# pa-test-board_V2.net
KiCad netlist of a schematic drawn in EAGLE
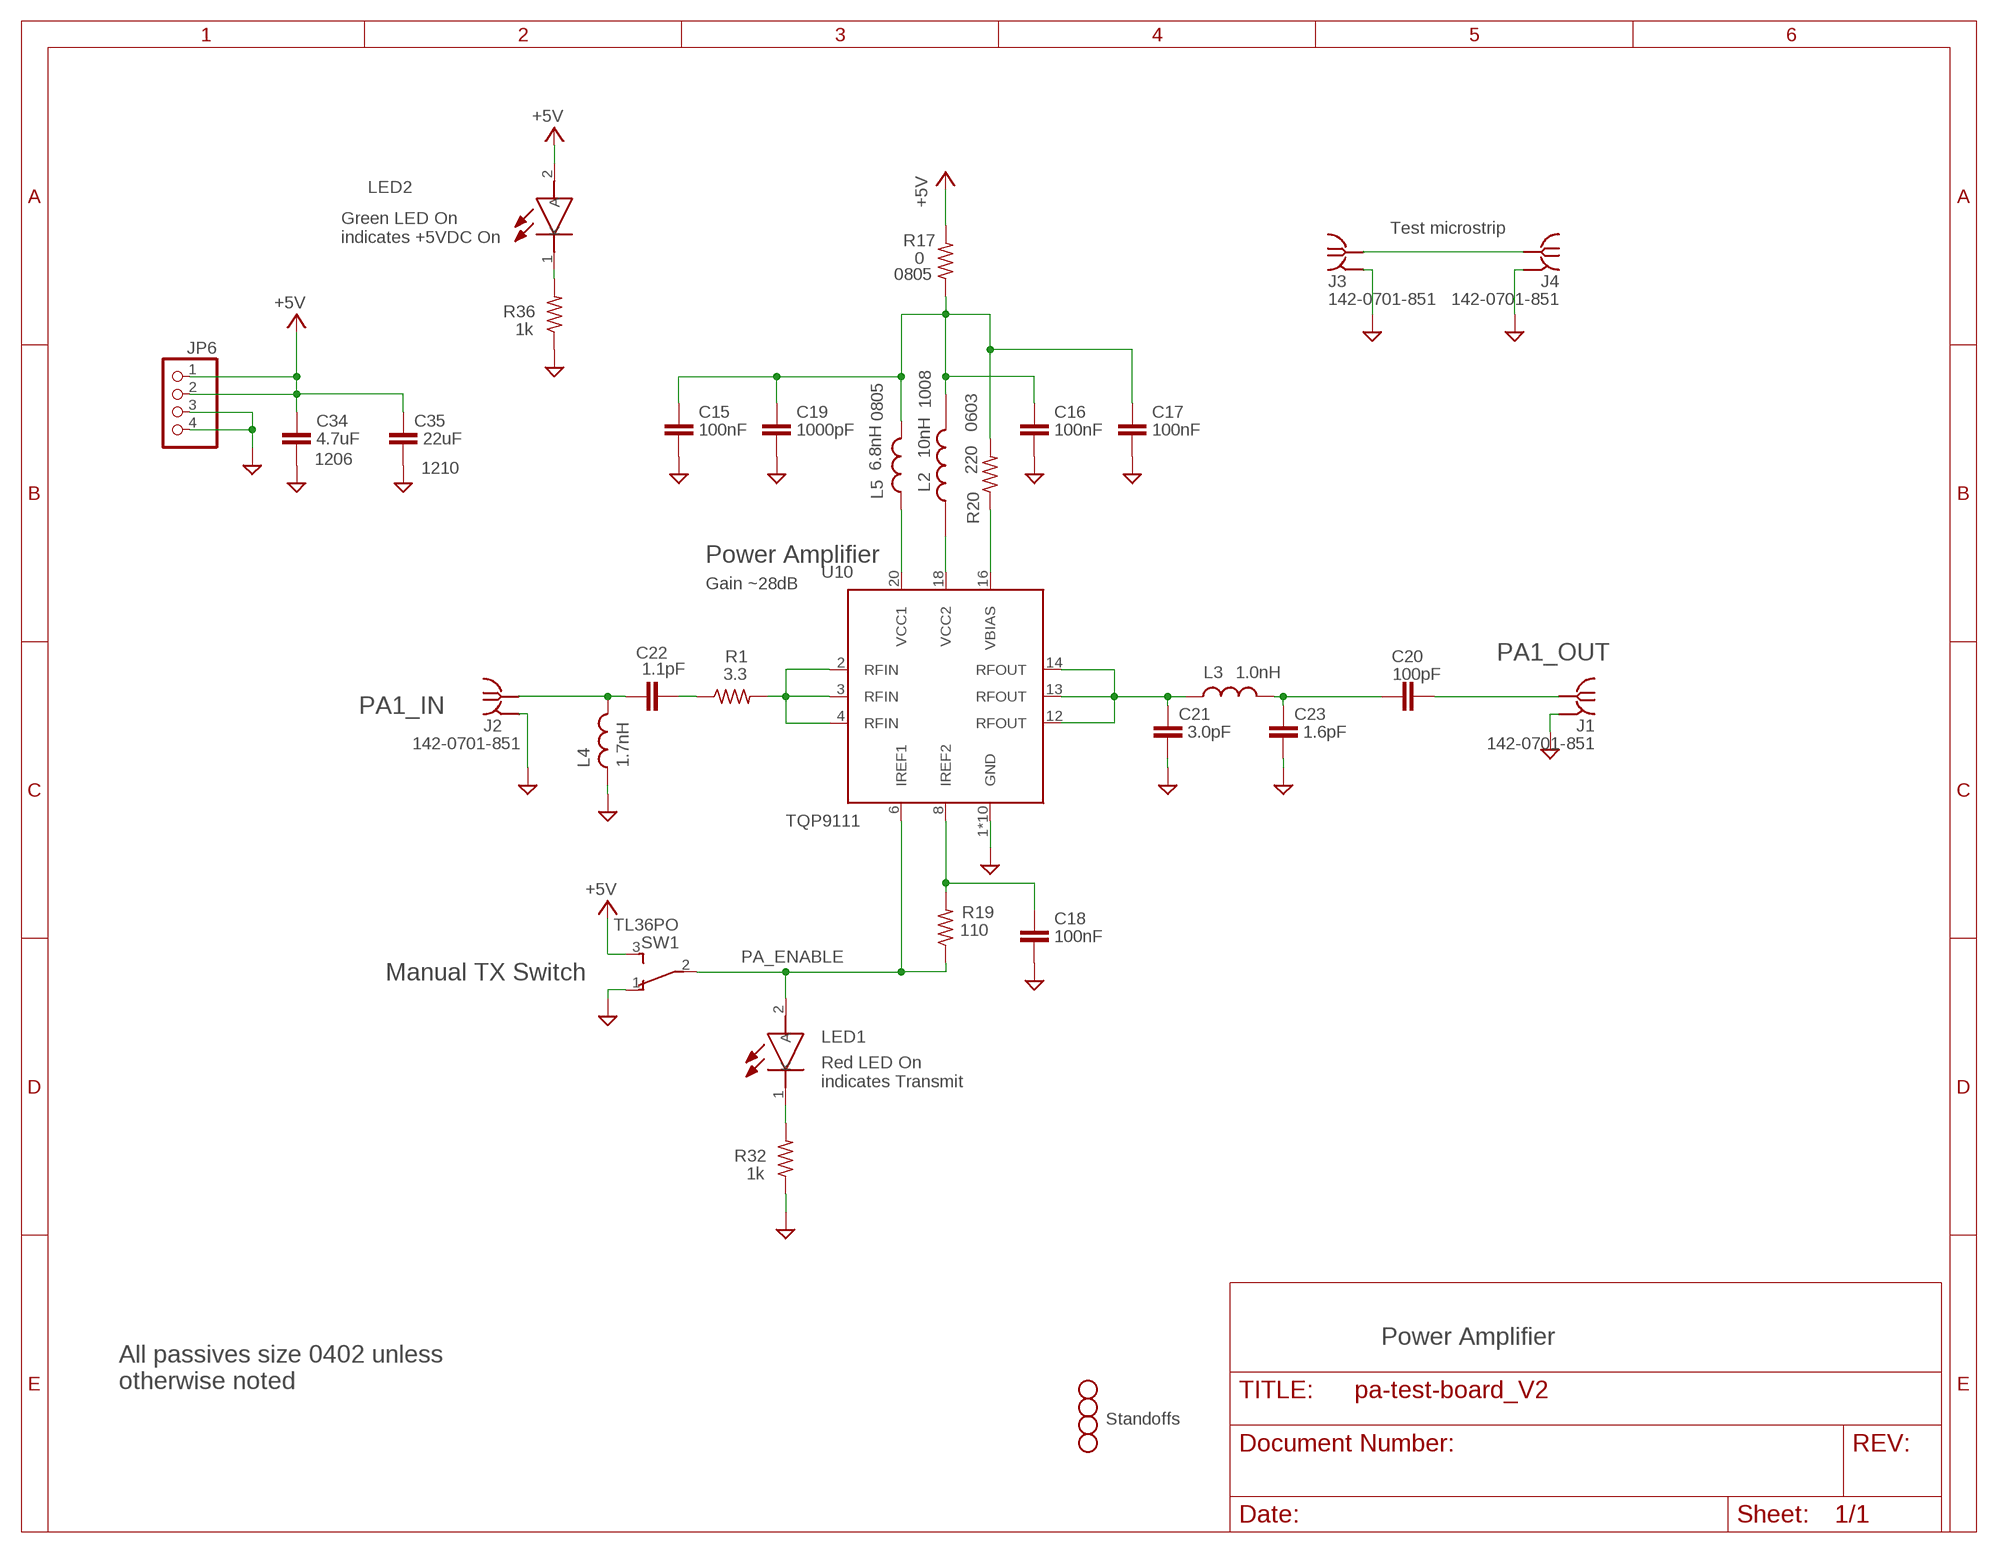
[diagram p0: schematic, sheet 1]

(export (version "E")
  (design (tool "Eeschema 10.0.6"))
  (components
    (comp (ref "C15")
      (value "100nF")
      (footprint "eagle-import:.0402-B-NOSILK")
      (description "CAP CER 0.1UF 16V X7R 0402")
      (fields (field (name "MFR") "TDK") (field (name "MPN") "CGA2B1X7R1C104K050BC"))
      (libsource (lib "eagle-import") (part "C-EU0402-B-NOSILK"))
    )
    (comp (ref "C16")
      (value "100nF")
      (footprint "eagle-import:.0402-B-NOSILK")
      (description "CAP CER 0.1UF 16V X7R 0402")
      (fields (field (name "MFR") "TDK") (field (name "MPN") "CGA2B1X7R1C104K050BC"))
      (libsource (lib "eagle-import") (part "C-EU0402-B-NOSILK"))
    )
    (comp (ref "C17")
      (value "100nF")
      (footprint "eagle-import:.0402-B-NOSILK")
      (description "CAP CER 0.1UF 16V X7R 0402")
      (fields (field (name "MFR") "TDK") (field (name "MPN") "CGA2B1X7R1C104K050BC"))
      (libsource (lib "eagle-import") (part "C-EU0402-B-NOSILK"))
    )
    (comp (ref "C18")
      (value "100nF")
      (footprint "eagle-import:.0402-C-NOSILK")
      (description "CAP CER 0.1UF 16V X7R 0402")
      (fields (field (name "MFR") "TDK") (field (name "MPN") "CGA2B1X7R1C104K050BC"))
      (libsource (lib "eagle-import") (part "C-EU0402-C-NOSILK"))
    )
    (comp (ref "C19")
      (value "1000pF")
      (footprint "eagle-import:.0402-B-NOSILK")
      (description "CAP CER 1000PF 50V NP0 0402")
      (fields (field (name "MFR") "TDK") (field (name "MPN") "CGA2B2NP01H102J050BA"))
      (libsource (lib "eagle-import") (part "C-EU0402-B-NOSILK"))
    )
    (comp (ref "C20")
      (value "100pF")
      (footprint "eagle-import:.0402-C-NOSILK")
      (description "CAP CER 100PF 50V C0G/NP0 0603")
      (fields (field (name "MFR") "Murata") (field (name "MPN") "GCM1885C1H101JA16D "))
      (libsource (lib "eagle-import") (part "C-EU0402-C-NOSILK"))
    )
    (comp (ref "C21")
      (value "3.0pF")
      (footprint "eagle-import:.0402-C-NOSILK")
      (description "CAP CER 3PF 50V NP0 0402")
      (fields (field (name "MFR") "AVX") (field (name "MPN") "04025U3R0BAT2A"))
      (libsource (lib "eagle-import") (part "C-EU0402-C-NOSILK"))
    )
    (comp (ref "C22")
      (value "1.1pF")
      (footprint "eagle-import:.0402-C-NOSILK")
      (description "50V 1.1pF .02pFTol ThinFilm 0402")
      (fields (field (name "MFR") "AVX") (field (name "MPN") "04025J1R1PBSTR\\500"))
      (libsource (lib "eagle-import") (part "C-EU0402-C-NOSILK"))
    )
    (comp (ref "C23")
      (value "1.6pF")
      (footprint "eagle-import:.0402-C-NOSILK")
      (description "CAP CER 1.6PF 50V NP0 0402")
      (fields (field (name "MFR") "AVX") (field (name "MPN") "04025U1R6BAT2A"))
      (libsource (lib "eagle-import") (part "C-EU0402-C-NOSILK"))
    )
    (comp (ref "C34")
      (value "4.7uF")
      (footprint "eagle-import:C1206")
      (description "CAP CER 4.7UF 16V X7R 1206")
      (fields (field (name "MFR") "Murata") (field (name "MPN") "GCJ31CR71C475KA01L"))
      (libsource (lib "eagle-import") (part "rcl_334_C-EUC1206"))
    )
    (comp (ref "C35")
      (value "22uF")
      (footprint "eagle-import:C1210")
      (description "CAP CER 22UF 16V X7R 1210")
      (fields (field (name "MFR") "Murata") (field (name "MPN") "GCJ32ER71C226KE01L"))
      (libsource (lib "eagle-import") (part "rcl_334_C-EUC1210"))
    )
    (comp (ref "H1")
      (value "STAND-OFFTIGHT")
      (footprint "eagle-import:STAND-OFF-TIGHT")
      (libsource (lib "eagle-import") (part "STAND-OFFTIGHT"))
    )
    (comp (ref "H2")
      (value "STAND-OFFTIGHT")
      (footprint "eagle-import:STAND-OFF-TIGHT")
      (libsource (lib "eagle-import") (part "STAND-OFFTIGHT"))
    )
    (comp (ref "H3")
      (value "STAND-OFFTIGHT")
      (footprint "eagle-import:STAND-OFF-TIGHT")
      (libsource (lib "eagle-import") (part "STAND-OFFTIGHT"))
    )
    (comp (ref "H4")
      (value "STAND-OFFTIGHT")
      (footprint "eagle-import:STAND-OFF-TIGHT")
      (libsource (lib "eagle-import") (part "STAND-OFFTIGHT"))
    )
    (comp (ref "J1")
      (value "142-0701-851")
      (footprint "eagle-import:142-0701-851")
      (description "CONN SMA JACK STR 50OHM EDGE MNT")
      (fields (field (name "MFR") "Cinch Connectivity Solutions Johnson"))
      (libsource (lib "eagle-import") (part "142-0701-851"))
    )
    (comp (ref "J2")
      (value "142-0701-851")
      (footprint "eagle-import:142-0701-851")
      (description "CONN SMA JACK STR 50OHM EDGE MNT")
      (fields (field (name "MFR") "Cinch Connectivity Solutions Johnson"))
      (libsource (lib "eagle-import") (part "142-0701-851"))
    )
    (comp (ref "J3")
      (value "142-0701-851")
      (footprint "eagle-import:142-0701-851")
      (description "CONN SMA JACK STR 50OHM EDGE MNT")
      (fields (field (name "MFR") "Cinch Connectivity Solutions Johnson"))
      (libsource (lib "eagle-import") (part "142-0701-851"))
    )
    (comp (ref "J4")
      (value "142-0701-851")
      (footprint "eagle-import:142-0701-851")
      (description "CONN SMA JACK STR 50OHM EDGE MNT")
      (fields (field (name "MFR") "Cinch Connectivity Solutions Johnson"))
      (libsource (lib "eagle-import") (part "142-0701-851"))
    )
    (comp (ref "JP6")
      (value "PINHD-1X4")
      (footprint "eagle-import:1X04")
      (description "CONN HEADER VERT 4POS 2.54MM")
      (fields (field (name "MFR") "Molex") (field (name "MPN") "0022232041"))
      (libsource (lib "eagle-import") (part "PINHD-1X4"))
    )
    (comp (ref "L2")
      (value "10nH")
      (footprint "eagle-import:INDC2928X203N")
      (description "Fixed Inductors 1008 10nH Unshld 5% 1.6A 60mOhms")
      (fields (field (name "MFR") "COILCRAFT") (field (name "MPN") "1008HQ-10NXJLB"))
      (libsource (lib "eagle-import") (part "1008HQ-10NXJLB"))
    )
    (comp (ref "L3")
      (value "1.0nH")
      (footprint "eagle-import:.0402-C-NOSILK")
      (description "FIXED IND 1NH 500MA 100 MOHM SMD")
      (fields (field (name "MFR") "TDK Corporation") (field (name "MPN") "MLK1005S1N0ST000"))
      (libsource (lib "eagle-import") (part "L-US0402-C-NOSILK"))
    )
    (comp (ref "L4")
      (value "1.7nH")
      (footprint "eagle-import:.0402-C-NOSILK")
      (description "1.7nH RF Inductor, ceramic core, 5% tol, SMT, RoHS")
      (fields (field (name "MFR") "Coilcraft") (field (name "MPN") "0402DC-1N7XJRU"))
      (libsource (lib "eagle-import") (part "L-US0402-C-NOSILK"))
    )
    (comp (ref "L5")
      (value "6.8nH")
      (footprint "eagle-import:.0805-C-NOSILK")
      (description "Fixed Inductors 0805CS 6.8 nH 5 % 0.6 A")
      (fields (field (name "MFR") "Coilcraft") (field (name "MPN") "0805CS-060XJLC"))
      (libsource (lib "eagle-import") (part "L-US0805-C-NOSILK"))
    )
    (comp (ref "LED1")
      (value "LTST-C193KRKT-5A")
      (footprint "eagle-import:LEDC1607X80N")
      (fields (field (name "MFR") "Lite-On"))
      (libsource (lib "eagle-import") (part "LTST-C193KRKT-5A"))
    )
    (comp (ref "LED2")
      (value "LTST-C193KGKT-5A")
      (footprint "eagle-import:LEDC1607X80N")
      (fields (field (name "MFR") "Lite-On"))
      (libsource (lib "eagle-import") (part "LTST-C193KGKT-5A"))
    )
    (comp (ref "R1")
      (value "3.3")
      (footprint "eagle-import:.0402-C-NOSILK")
      (description "Resistor- SMD 1/16watt 3.3ohms 1% 100ppm")
      (fields (field (name "MFR") "Vishay / Dale") (field (name "MPN") "CRCW04023R30FKED"))
      (libsource (lib "eagle-import") (part "R-US_0402-C-NOSILK"))
    )
    (comp (ref "R17")
      (value "0")
      (footprint "eagle-import:R0805")
      (description "RES SMD 0 OHM JUMPER 1/8W 0805")
      (fields (field (name "MFR") "Panasonic") (field (name "MPN") "ERJ-6GEY0R00V"))
      (libsource (lib "eagle-import") (part "rcl_334_R-US_R0805"))
    )
    (comp (ref "R19")
      (value "110")
      (footprint "eagle-import:.0402-B-NOSILK")
      (description "RES SMD 110 OHM 1% 1/10W 0402")
      (fields (field (name "MFR") "Panasonic") (field (name "MPN") "ERJ-2RKF1100X"))
      (libsource (lib "eagle-import") (part "R-US_0402-B-NOSILK"))
    )
    (comp (ref "R20")
      (value "220")
      (footprint "eagle-import:.0603-C-NOSILK")
      (description "RES SMD 220 OHM 1% 1/10W 0603")
      (fields (field (name "MFR") "Panasonic") (field (name "MPN") "ERJ-3EKF2200V"))
      (libsource (lib "eagle-import") (part "R-US_0603-C-NOSILK"))
    )
    (comp (ref "R32")
      (value "1k")
      (footprint "eagle-import:.0402-B-NOSILK")
      (description "RES SMD 1K OHM 5% 1/10W 0402")
      (fields (field (name "MFR") "Panasonic") (field (name "MPN") "ERJ-2GEJ102X"))
      (libsource (lib "eagle-import") (part "R-US_0402-B-NOSILK"))
    )
    (comp (ref "R36")
      (value "1k")
      (footprint "eagle-import:.0402-B-NOSILK")
      (description "RES SMD 1K OHM 5% 1/10W 0402")
      (fields (field (name "MFR") "Panasonic") (field (name "MPN") "ERJ-2GEJ102X"))
      (libsource (lib "eagle-import") (part "R-US_0402-B-NOSILK"))
    )
    (comp (ref "SW1")
      (value "TL36PO")
      (footprint "eagle-import:TL3XPO")
      (description "SWITCH TOGGLE SPDT 0.4VA 20V")
      (fields (field (name "MFR") "APEM Inc.") (field (name "MPN") "TL36P005000"))
      (libsource (lib "eagle-import") (part "TL36PO"))
    )
    (comp (ref "U10")
      (value "TQP9111")
      (footprint "eagle-import:QFN50P400X400X102-21N")
      (fields (field (name "MFR") "Qorvo"))
      (libsource (lib "eagle-import") (part "TQP9111"))
    )
  )
  (nets
    (net (code "1") (name "+5V") (class "Default")
      (node (ref "C34") (pin "1") (pinfunction "1_1") (pintype "passive"))
      (node (ref "C35") (pin "1") (pinfunction "1_1") (pintype "passive"))
      (node (ref "JP6") (pin "1") (pinfunction "1_1") (pintype "passive"))
      (node (ref "JP6") (pin "2") (pinfunction "2_2") (pintype "passive"))
      (node (ref "LED2") (pin "2") (pinfunction "A_2") (pintype "bidirectional"))
      (node (ref "R17") (pin "2") (pinfunction "2_2") (pintype "passive"))
      (node (ref "SW1") (pin "3") (pinfunction "S_3") (pintype "passive"))
    )
    (net (code "2") (name "/PA1_OUT") (class "Default")
      (node (ref "C20") (pin "2") (pinfunction "2_2") (pintype "passive"))
      (node (ref "J1") (pin "RF1") (pinfunction "RF_RF1") (pintype "bidirectional"))
    )
    (net (code "3") (name "/PA_ENABLE") (class "Default")
      (node (ref "LED1") (pin "2") (pinfunction "A_2") (pintype "bidirectional"))
      (node (ref "R19") (pin "1") (pinfunction "1_1") (pintype "passive"))
      (node (ref "SW1") (pin "2") (pinfunction "P_2") (pintype "passive"))
      (node (ref "U10") (pin "6") (pinfunction "IREF1_6") (pintype "passive"))
    )
    (net (code "4") (name "GND") (class "Default")
      (node (ref "C15") (pin "2") (pinfunction "2_2") (pintype "passive"))
      (node (ref "C16") (pin "2") (pinfunction "2_2") (pintype "passive"))
      (node (ref "C17") (pin "2") (pinfunction "2_2") (pintype "passive"))
      (node (ref "C18") (pin "2") (pinfunction "2_2") (pintype "passive"))
      (node (ref "C19") (pin "2") (pinfunction "2_2") (pintype "passive"))
      (node (ref "C21") (pin "2") (pinfunction "2_2") (pintype "passive"))
      (node (ref "C23") (pin "2") (pinfunction "2_2") (pintype "passive"))
      (node (ref "C34") (pin "2") (pinfunction "2_2") (pintype "passive"))
      (node (ref "C35") (pin "2") (pinfunction "2_2") (pintype "passive"))
      (node (ref "J1") (pin "GND1") (pinfunction "GND_GND1") (pintype "bidirectional"))
      (node (ref "J1") (pin "GND2") (pinfunction "GND_GND2") (pintype "bidirectional"))
      (node (ref "J1") (pin "GND3") (pinfunction "GND_GND3") (pintype "bidirectional"))
      (node (ref "J1") (pin "GND4") (pinfunction "GND_GND4") (pintype "bidirectional"))
      (node (ref "J2") (pin "GND1") (pinfunction "GND_GND1") (pintype "bidirectional"))
      (node (ref "J2") (pin "GND2") (pinfunction "GND_GND2") (pintype "bidirectional"))
      (node (ref "J2") (pin "GND3") (pinfunction "GND_GND3") (pintype "bidirectional"))
      (node (ref "J2") (pin "GND4") (pinfunction "GND_GND4") (pintype "bidirectional"))
      (node (ref "J3") (pin "GND1") (pinfunction "GND_GND1") (pintype "bidirectional"))
      (node (ref "J3") (pin "GND2") (pinfunction "GND_GND2") (pintype "bidirectional"))
      (node (ref "J3") (pin "GND3") (pinfunction "GND_GND3") (pintype "bidirectional"))
      (node (ref "J3") (pin "GND4") (pinfunction "GND_GND4") (pintype "bidirectional"))
      (node (ref "J4") (pin "GND1") (pinfunction "GND_GND1") (pintype "bidirectional"))
      (node (ref "J4") (pin "GND2") (pinfunction "GND_GND2") (pintype "bidirectional"))
      (node (ref "J4") (pin "GND3") (pinfunction "GND_GND3") (pintype "bidirectional"))
      (node (ref "J4") (pin "GND4") (pinfunction "GND_GND4") (pintype "bidirectional"))
      (node (ref "JP6") (pin "3") (pinfunction "3_3") (pintype "passive"))
      (node (ref "JP6") (pin "4") (pinfunction "4_4") (pintype "passive"))
      (node (ref "L4") (pin "1") (pinfunction "1_1") (pintype "passive"))
      (node (ref "R32") (pin "1") (pinfunction "1_1") (pintype "passive"))
      (node (ref "R36") (pin "1") (pinfunction "1_1") (pintype "passive"))
      (node (ref "SW1") (pin "1") (pinfunction "O_1") (pintype "passive"))
      (node (ref "U10") (pin "1") (pinfunction "GND_1") (pintype "power_in"))
      (node (ref "U10") (pin "10") (pinfunction "GND_10") (pintype "power_in"))
      (node (ref "U10") (pin "11") (pinfunction "GND_11") (pintype "power_in"))
      (node (ref "U10") (pin "15") (pinfunction "GND_15") (pintype "power_in"))
      (node (ref "U10") (pin "17") (pinfunction "GND_17") (pintype "power_in"))
      (node (ref "U10") (pin "19") (pinfunction "GND_19") (pintype "power_in"))
      (node (ref "U10") (pin "21") (pinfunction "GND_21") (pintype "power_in"))
      (node (ref "U10") (pin "5") (pinfunction "GND_5") (pintype "power_in"))
      (node (ref "U10") (pin "7") (pinfunction "GND_7") (pintype "power_in"))
      (node (ref "U10") (pin "9") (pinfunction "GND_9") (pintype "power_in"))
    )
    (net (code "5") (name "Net-(C15-Pad1)") (class "Default")
      (node (ref "C15") (pin "1") (pinfunction "1_1") (pintype "passive"))
      (node (ref "C16") (pin "1") (pinfunction "1_1") (pintype "passive"))
      (node (ref "C17") (pin "1") (pinfunction "1_1") (pintype "passive"))
      (node (ref "C19") (pin "1") (pinfunction "1_1") (pintype "passive"))
      (node (ref "L2") (pin "2") (pinfunction "2_2") (pintype "bidirectional"))
      (node (ref "L5") (pin "2") (pinfunction "2_2") (pintype "passive"))
      (node (ref "R17") (pin "1") (pinfunction "1_1") (pintype "passive"))
      (node (ref "R20") (pin "2") (pinfunction "2_2") (pintype "passive"))
    )
    (net (code "6") (name "Net-(C20-Pad1)") (class "Default")
      (node (ref "C20") (pin "1") (pinfunction "1_1") (pintype "passive"))
      (node (ref "C23") (pin "1") (pinfunction "1_1") (pintype "passive"))
      (node (ref "L3") (pin "2") (pinfunction "2_2") (pintype "passive"))
    )
    (net (code "7") (name "Net-(C21-Pad1)") (class "Default")
      (node (ref "C21") (pin "1") (pinfunction "1_1") (pintype "passive"))
      (node (ref "L3") (pin "1") (pinfunction "1_1") (pintype "passive"))
      (node (ref "U10") (pin "12") (pinfunction "RFOUT_12") (pintype "output"))
      (node (ref "U10") (pin "13") (pinfunction "RFOUT_13") (pintype "output"))
      (node (ref "U10") (pin "14") (pinfunction "RFOUT_14") (pintype "output"))
    )
    (net (code "8") (name "Net-(C22-Pad2)") (class "Default")
      (node (ref "C22") (pin "2") (pinfunction "2_2") (pintype "passive"))
      (node (ref "R1") (pin "1") (pinfunction "1_1") (pintype "passive"))
    )
    (net (code "9") (name "Net-(J2-RF)") (class "Default")
      (node (ref "C22") (pin "1") (pinfunction "1_1") (pintype "passive"))
      (node (ref "J2") (pin "RF1") (pinfunction "RF_RF1") (pintype "bidirectional"))
      (node (ref "L4") (pin "2") (pinfunction "2_2") (pintype "passive"))
    )
    (net (code "10") (name "Net-(J3-RF)") (class "Default")
      (node (ref "J3") (pin "RF1") (pinfunction "RF_RF1") (pintype "bidirectional"))
      (node (ref "J4") (pin "RF1") (pinfunction "RF_RF1") (pintype "bidirectional"))
    )
    (net (code "11") (name "Net-(LED1-K)") (class "Default")
      (node (ref "LED1") (pin "1") (pinfunction "K_1") (pintype "bidirectional"))
      (node (ref "R32") (pin "2") (pinfunction "2_2") (pintype "passive"))
    )
    (net (code "12") (name "Net-(LED2-K)") (class "Default")
      (node (ref "LED2") (pin "1") (pinfunction "K_1") (pintype "bidirectional"))
      (node (ref "R36") (pin "2") (pinfunction "2_2") (pintype "passive"))
    )
    (net (code "13") (name "Net-(R1-Pad2)") (class "Default")
      (node (ref "R1") (pin "2") (pinfunction "2_2") (pintype "passive"))
      (node (ref "U10") (pin "2") (pinfunction "RFIN_2") (pintype "input"))
      (node (ref "U10") (pin "3") (pinfunction "RFIN_3") (pintype "input"))
      (node (ref "U10") (pin "4") (pinfunction "RFIN_4") (pintype "input"))
    )
    (net (code "14") (name "Net-(U10-IREF2)") (class "Default")
      (node (ref "C18") (pin "1") (pinfunction "1_1") (pintype "passive"))
      (node (ref "R19") (pin "2") (pinfunction "2_2") (pintype "passive"))
      (node (ref "U10") (pin "8") (pinfunction "IREF2_8") (pintype "passive"))
    )
    (net (code "15") (name "Net-(U10-VBIAS)") (class "Default")
      (node (ref "R20") (pin "1") (pinfunction "1_1") (pintype "passive"))
      (node (ref "U10") (pin "16") (pinfunction "VBIAS_16") (pintype "power_in"))
    )
    (net (code "16") (name "Net-(U10-VCC1)") (class "Default")
      (node (ref "L5") (pin "1") (pinfunction "1_1") (pintype "passive"))
      (node (ref "U10") (pin "20") (pinfunction "VCC1_20") (pintype "power_in"))
    )
    (net (code "17") (name "Net-(U10-VCC2)") (class "Default")
      (node (ref "L2") (pin "1") (pinfunction "1_1") (pintype "bidirectional"))
      (node (ref "U10") (pin "18") (pinfunction "VCC2_18") (pintype "power_in"))
    )
  )
)
